# photodiode_board.net
KiCad netlist of a schematic drawn in EAGLE
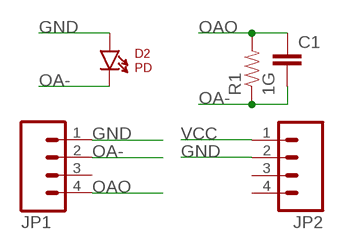
[diagram p0: schematic, sheet 1]

(export (version "E")
  (design (tool "Eeschema 10.0.6"))
  (components
    (comp (ref "C1")
      (value "CAPPTH")
      (footprint "eagle-import:CAP-PTH-SMALL")
      (libsource (lib "eagle-import") (part "CAPPTH"))
    )
    (comp (ref "D2")
      (value "PD")
      (footprint "eagle-import:LTE-302")
      (libsource (lib "eagle-import") (part "LTE-302"))
    )
    (comp (ref "JP1")
      (value "M04PTH")
      (footprint "eagle-import:1X04")
      (libsource (lib "eagle-import") (part "M04PTH"))
    )
    (comp (ref "JP2")
      (value "M04PTH")
      (footprint "eagle-import:1X04")
      (libsource (lib "eagle-import") (part "M04PTH"))
    )
    (comp (ref "R1")
      (value "1G")
      (footprint "eagle-import:AXIAL-0.3")
      (libsource (lib "eagle-import") (part "RESISTORAXIAL-0.3"))
    )
  )
  (nets
    (net (code "1") (name "/GND") (class "Default")
      (node (ref "D2") (pin "A") (pinfunction "A_A") (pintype "bidirectional"))
      (node (ref "JP1") (pin "1") (pinfunction "1_1") (pintype "passive"))
      (node (ref "JP2") (pin "2") (pinfunction "2_2") (pintype "passive"))
    )
    (net (code "2") (name "/OA-") (class "Default")
      (node (ref "C1") (pin "2") (pinfunction "2_2") (pintype "passive"))
      (node (ref "D2") (pin "C") (pinfunction "C_C") (pintype "bidirectional"))
      (node (ref "JP1") (pin "2") (pinfunction "2_2") (pintype "passive"))
      (node (ref "R1") (pin "P$1") (pinfunction "1_P$1") (pintype "passive"))
    )
    (net (code "3") (name "/OAO") (class "Default")
      (node (ref "C1") (pin "1") (pinfunction "1_1") (pintype "passive"))
      (node (ref "JP1") (pin "4") (pinfunction "4_4") (pintype "passive"))
      (node (ref "R1") (pin "P$2") (pinfunction "2_P$2") (pintype "passive"))
    )
    (net (code "4") (name "/VCC") (class "Default")
      (node (ref "JP2") (pin "1") (pinfunction "1_1") (pintype "passive"))
    )
    (net (code "5") (name "unconnected-(JP1-Pad3)") (class "Default")
      (node (ref "JP1") (pin "3") (pinfunction "3_3") (pintype "passive"))
    )
    (net (code "6") (name "unconnected-(JP2-Pad3)") (class "Default")
      (node (ref "JP2") (pin "3") (pinfunction "3_3") (pintype "passive"))
    )
    (net (code "7") (name "unconnected-(JP2-Pad4)") (class "Default")
      (node (ref "JP2") (pin "4") (pinfunction "4_4") (pintype "passive"))
    )
  )
)
